# paste_injectorMM.net
KiCad netlist of a schematic drawn in EAGLE
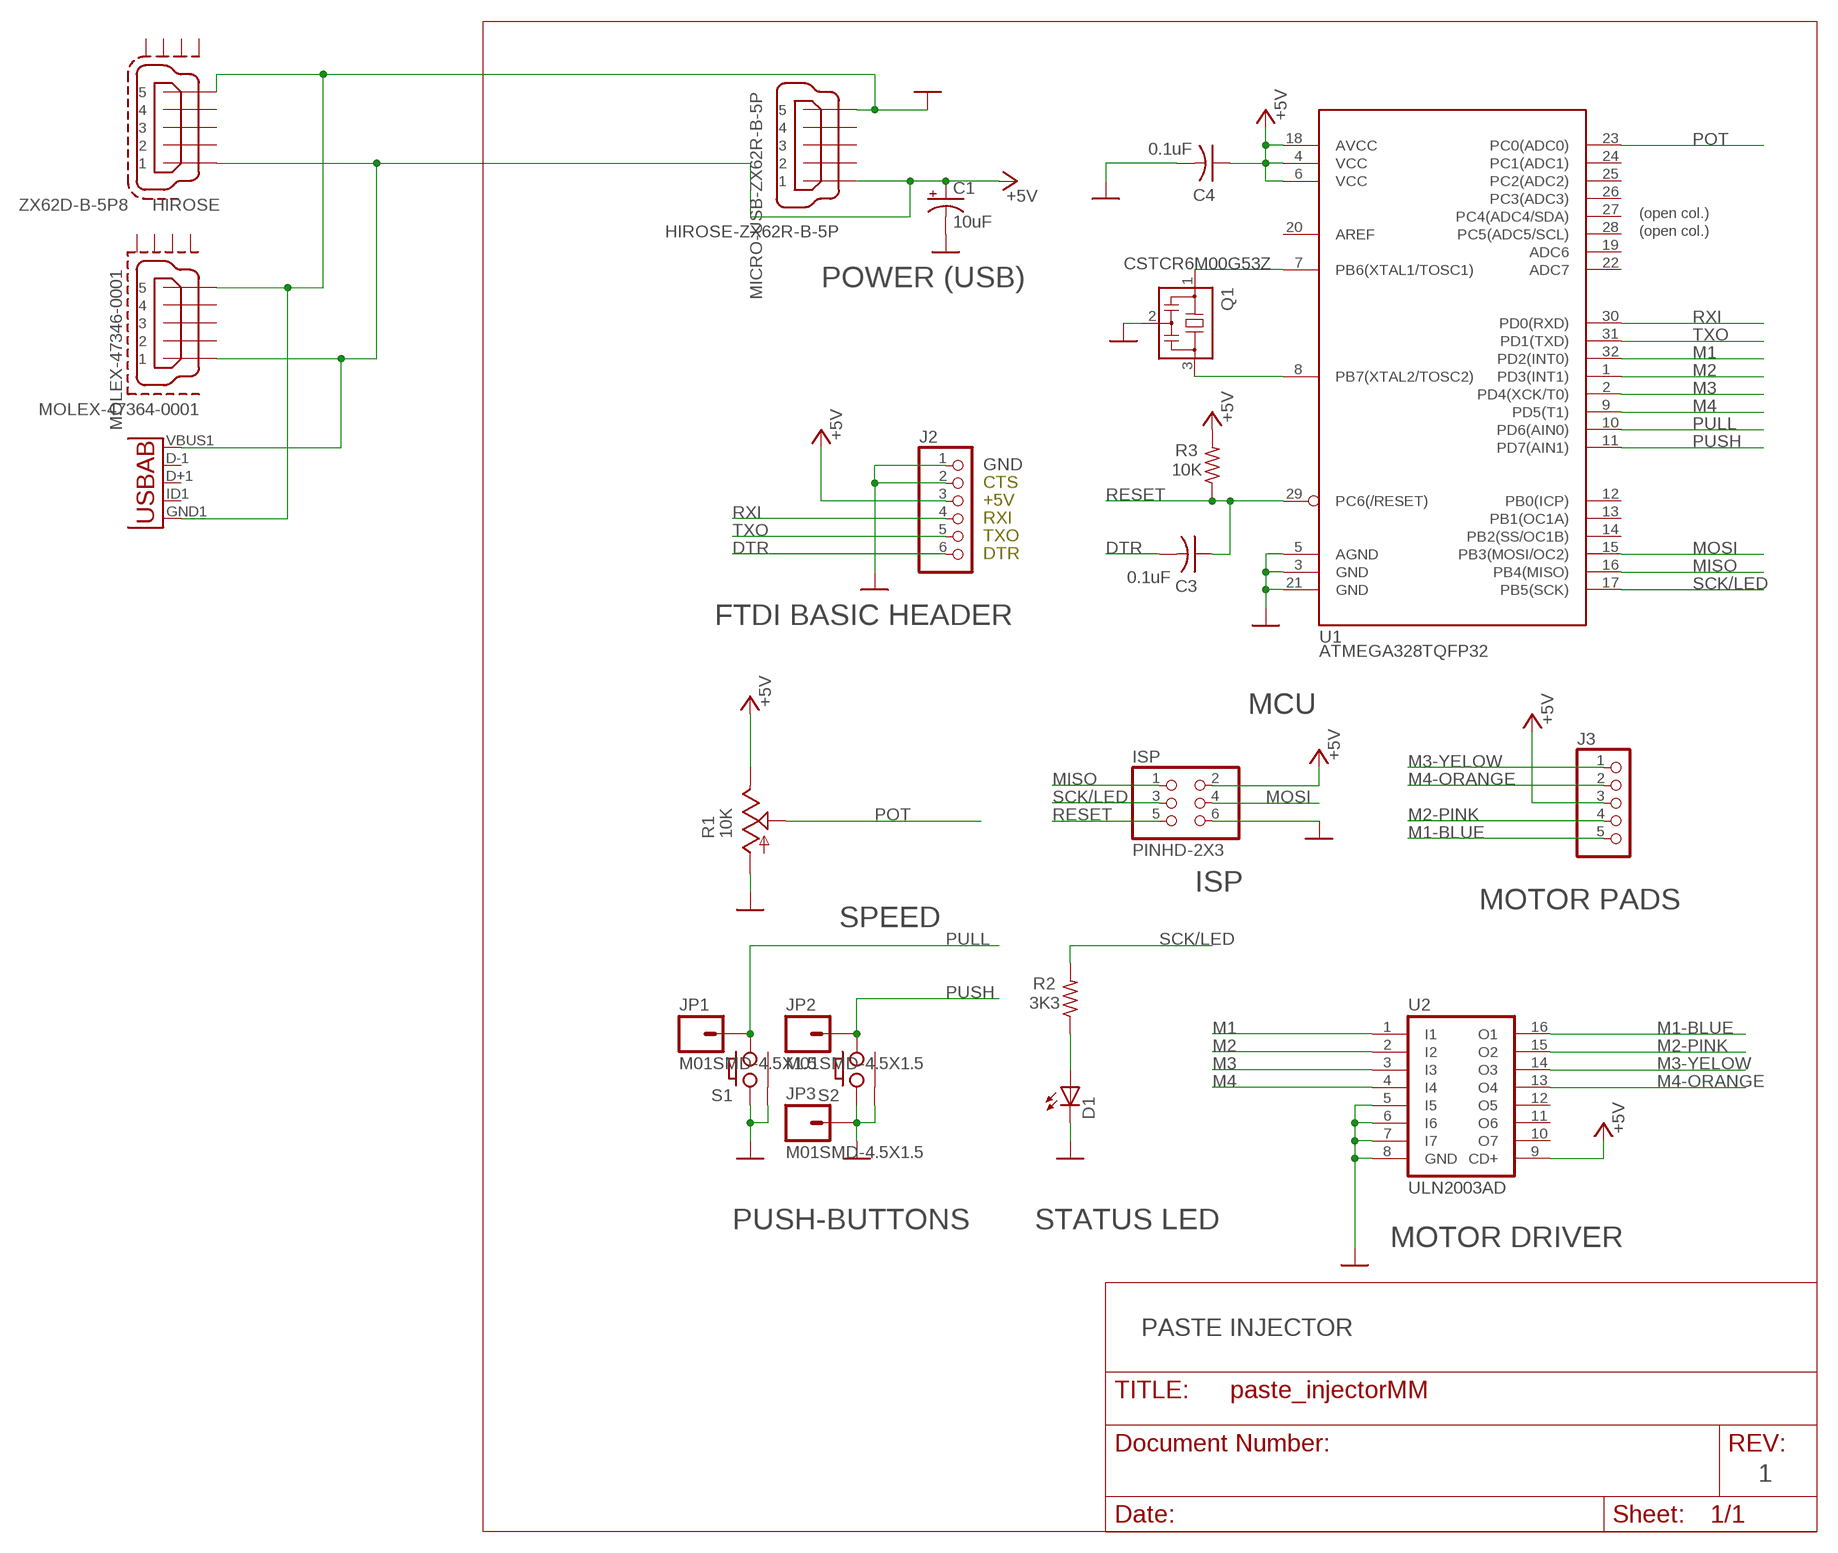
[diagram p0: schematic, sheet 1]

(export (version "E")
  (design (tool "Eeschema 10.0.6"))
  (components
    (comp (ref "C1")
      (value "10uF")
      (footprint "eagle-import:A_3216-18R")
      (libsource (lib "eagle-import") (part "CPOL-USA/3216-18R"))
    )
    (comp (ref "C3")
      (value "0.1uF")
      (footprint "eagle-import:C0603")
      (libsource (lib "eagle-import") (part "CAP-C0603"))
    )
    (comp (ref "C4")
      (value "0.1uF")
      (footprint "eagle-import:C0603")
      (libsource (lib "eagle-import") (part "CAP-C0603"))
    )
    (comp (ref "D1")
      (value "LED")
      (footprint "eagle-import:LED0603")
      (libsource (lib "eagle-import") (part "LED"))
    )
    (comp (ref "HIROSE")
      (value "ZX62D-B-5P8")
      (footprint "eagle-import:ZX62D-B-5P8")
      (libsource (lib "eagle-import") (part "ZX62D-B-5P8"))
    )
    (comp (ref "HIROSE-ZX62R-B-5P")
      (value "MICRO-USB-ZX62R-B-5P")
      (footprint "eagle-import:ZX62R-B-5P")
      (libsource (lib "eagle-import") (part "MICRO-USB-ZX62R-B-5P"))
    )
    (comp (ref "ISP")
      (value "PINHD-2X3")
      (footprint "eagle-import:2X03")
      (libsource (lib "eagle-import") (part "PINHD-2X3"))
    )
    (comp (ref "J2")
      (value "PINHD-1X6")
      (footprint "eagle-import:1X06")
      (libsource (lib "eagle-import") (part "PINHD-1X6"))
    )
    (comp (ref "J3")
      (value "PINHD-1X5")
      (footprint "eagle-import:1X05")
      (libsource (lib "eagle-import") (part "PINHD-1X5"))
    )
    (comp (ref "JP1")
      (value "M01SMD-4.5X1.5")
      (footprint "eagle-import:PAD-1.5X4.5")
      (libsource (lib "eagle-import") (part "M01SMD-4.5X1.5"))
    )
    (comp (ref "JP2")
      (value "M01SMD-4.5X1.5")
      (footprint "eagle-import:PAD-1.5X4.5")
      (libsource (lib "eagle-import") (part "M01SMD-4.5X1.5"))
    )
    (comp (ref "JP3")
      (value "M01SMD-4.5X1.5")
      (footprint "eagle-import:PAD-1.5X4.5")
      (libsource (lib "eagle-import") (part "M01SMD-4.5X1.5"))
    )
    (comp (ref "MOLEX-47364-0001")
      (value "MOLEX-47346-0001")
      (footprint "eagle-import:MOLEX-47364-0001")
      (libsource (lib "eagle-import") (part "MOLEX-47346-0001"))
    )
    (comp (ref "Q1")
      (value "CSTCR6M00G53Z")
      (footprint "eagle-import:CSTCR6M")
      (fields (field (name "MPN") "CSTCR6M00G53-R0"))
      (libsource (lib "eagle-import") (part "CSTCR6M00G53Z"))
    )
    (comp (ref "R1")
      (value "10K")
      (footprint "eagle-import:TRIMPOT")
      (libsource (lib "eagle-import") (part "TRIMPOTCA9V"))
    )
    (comp (ref "R2")
      (value "3K3")
      (footprint "eagle-import:R0603")
      (libsource (lib "eagle-import") (part "RES-R0603"))
    )
    (comp (ref "R3")
      (value "10K")
      (footprint "eagle-import:R0603")
      (libsource (lib "eagle-import") (part "RES-R0603"))
    )
    (comp (ref "S1")
      (value "PUSH_BUTTON")
      (footprint "eagle-import:PUSH_BUTTON")
      (libsource (lib "eagle-import") (part "PUSH_BUTTON"))
    )
    (comp (ref "S2")
      (value "PUSH_BUTTON")
      (footprint "eagle-import:PUSH_BUTTON")
      (libsource (lib "eagle-import") (part "PUSH_BUTTON"))
    )
    (comp (ref "U$7")
      (value "USB-AB\"\"")
      (footprint "eagle-import:USB-AB-MICRO-SMD_V02_BOSS")
      (libsource (lib "eagle-import") (part "USB-AB{dblquote}{dblquote}"))
    )
    (comp (ref "U1")
      (value "ATMEGA328TQFP32")
      (footprint "eagle-import:TQFP32-08")
      (libsource (lib "eagle-import") (part "ATMEGA328TQFP32"))
    )
    (comp (ref "U2")
      (value "ULN2003AD")
      (footprint "eagle-import:SO16")
      (libsource (lib "eagle-import") (part "ULN2003AD"))
    )
  )
  (nets
    (net (code "1") (name "+5V") (class "Default")
      (node (ref "C1") (pin "+") (pinfunction "+_+") (pintype "passive"))
      (node (ref "C4") (pin "1") (pinfunction "1_1") (pintype "passive"))
      (node (ref "HIROSE") (pin "P$1") (pinfunction "1_P$1") (pintype "passive"))
      (node (ref "HIROSE-ZX62R-B-5P") (pin "1") (pinfunction "1_1") (pintype "input"))
      (node (ref "ISP") (pin "2") (pinfunction "2_2") (pintype "passive"))
      (node (ref "J2") (pin "3") (pinfunction "3_3") (pintype "passive"))
      (node (ref "J3") (pin "3") (pinfunction "3_3") (pintype "passive"))
      (node (ref "MOLEX-47364-0001") (pin "1") (pinfunction "1_1") (pintype "input"))
      (node (ref "R1") (pin "CW") (pinfunction "CW_CW") (pintype "passive"))
      (node (ref "R3") (pin "2") (pinfunction "2_2") (pintype "passive"))
      (node (ref "U$7") (pin "VBUS1") (pinfunction "VBUS_VBUS1") (pintype "bidirectional"))
      (node (ref "U1") (pin "18") (pinfunction "AVCC_18") (pintype "power_in"))
      (node (ref "U1") (pin "4") (pinfunction "VCC_4") (pintype "power_in"))
      (node (ref "U1") (pin "6") (pinfunction "VCC_6") (pintype "power_in"))
      (node (ref "U2") (pin "9") (pinfunction "CD+_9") (pintype "passive"))
    )
    (net (code "2") (name "/AREF") (class "Default")
      (node (ref "U1") (pin "20") (pinfunction "AREF_20") (pintype "power_in"))
    )
    (net (code "3") (name "/DTR") (class "Default")
      (node (ref "C3") (pin "2") (pinfunction "2_2") (pintype "passive"))
      (node (ref "J2") (pin "6") (pinfunction "6_6") (pintype "passive"))
    )
    (net (code "4") (name "/M1") (class "Default")
      (node (ref "U1") (pin "32") (pinfunction "PD2(INT0)_32") (pintype "bidirectional"))
      (node (ref "U2") (pin "1") (pinfunction "I1_1") (pintype "input"))
    )
    (net (code "5") (name "/M1-BLUE") (class "Default")
      (node (ref "J3") (pin "5") (pinfunction "5_5") (pintype "passive"))
      (node (ref "U2") (pin "16") (pinfunction "O1_16") (pintype "open_collector"))
    )
    (net (code "6") (name "/M2") (class "Default")
      (node (ref "U1") (pin "1") (pinfunction "PD3(INT1)_1") (pintype "bidirectional"))
      (node (ref "U2") (pin "2") (pinfunction "I2_2") (pintype "input"))
    )
    (net (code "7") (name "/M2-PINK") (class "Default")
      (node (ref "J3") (pin "4") (pinfunction "4_4") (pintype "passive"))
      (node (ref "U2") (pin "15") (pinfunction "O2_15") (pintype "open_collector"))
    )
    (net (code "8") (name "/M3") (class "Default")
      (node (ref "U1") (pin "2") (pinfunction "PD4(XCK/T0)_2") (pintype "bidirectional"))
      (node (ref "U2") (pin "3") (pinfunction "I3_3") (pintype "input"))
    )
    (net (code "9") (name "/M3-YELOW") (class "Default")
      (node (ref "J3") (pin "1") (pinfunction "1_1") (pintype "passive"))
      (node (ref "U2") (pin "14") (pinfunction "O3_14") (pintype "open_collector"))
    )
    (net (code "10") (name "/M4") (class "Default")
      (node (ref "U1") (pin "9") (pinfunction "PD5(T1)_9") (pintype "bidirectional"))
      (node (ref "U2") (pin "4") (pinfunction "I4_4") (pintype "input"))
    )
    (net (code "11") (name "/M4-ORANGE") (class "Default")
      (node (ref "J3") (pin "2") (pinfunction "2_2") (pintype "passive"))
      (node (ref "U2") (pin "13") (pinfunction "O4_13") (pintype "open_collector"))
    )
    (net (code "12") (name "/MISO") (class "Default")
      (node (ref "ISP") (pin "1") (pinfunction "1_1") (pintype "passive"))
      (node (ref "U1") (pin "16") (pinfunction "PB4(MISO)_16") (pintype "bidirectional"))
    )
    (net (code "13") (name "/MOSI") (class "Default")
      (node (ref "ISP") (pin "4") (pinfunction "4_4") (pintype "passive"))
      (node (ref "U1") (pin "15") (pinfunction "PB3(MOSI/OC2)_15") (pintype "bidirectional"))
    )
    (net (code "14") (name "/POT") (class "Default")
      (node (ref "R1") (pin "C") (pinfunction "C_C") (pintype "passive"))
      (node (ref "U1") (pin "23") (pinfunction "PC0(ADC0)_23") (pintype "bidirectional"))
    )
    (net (code "15") (name "/PULL") (class "Default")
      (node (ref "JP1") (pin "P$1") (pinfunction "1_P$1") (pintype "passive"))
      (node (ref "S1") (pin "B1") (pinfunction "2_B1") (pintype "passive"))
      (node (ref "U1") (pin "10") (pinfunction "PD6(AIN0)_10") (pintype "bidirectional"))
    )
    (net (code "16") (name "/PUSH") (class "Default")
      (node (ref "JP2") (pin "P$1") (pinfunction "1_P$1") (pintype "passive"))
      (node (ref "S2") (pin "B1") (pinfunction "2_B1") (pintype "passive"))
      (node (ref "U1") (pin "11") (pinfunction "PD7(AIN1)_11") (pintype "bidirectional"))
    )
    (net (code "17") (name "/RESET") (class "Default")
      (node (ref "C3") (pin "1") (pinfunction "1_1") (pintype "passive"))
      (node (ref "ISP") (pin "5") (pinfunction "5_5") (pintype "passive"))
      (node (ref "R3") (pin "1") (pinfunction "1_1") (pintype "passive"))
      (node (ref "U1") (pin "29") (pinfunction "PC6(/RESET)_29") (pintype "bidirectional"))
    )
    (net (code "18") (name "/RXI") (class "Default")
      (node (ref "J2") (pin "4") (pinfunction "4_4") (pintype "passive"))
      (node (ref "U1") (pin "30") (pinfunction "PD0(RXD)_30") (pintype "bidirectional"))
    )
    (net (code "19") (name "/SCK{slash}LED") (class "Default")
      (node (ref "ISP") (pin "3") (pinfunction "3_3") (pintype "passive"))
      (node (ref "R2") (pin "2") (pinfunction "2_2") (pintype "passive"))
      (node (ref "U1") (pin "17") (pinfunction "PB5(SCK)_17") (pintype "bidirectional"))
    )
    (net (code "20") (name "/TXO") (class "Default")
      (node (ref "J2") (pin "5") (pinfunction "5_5") (pintype "passive"))
      (node (ref "U1") (pin "31") (pinfunction "PD1(TXD)_31") (pintype "bidirectional"))
    )
    (net (code "21") (name "GND") (class "Default")
      (node (ref "C1") (pin "-") (pinfunction "-_-") (pintype "passive"))
      (node (ref "C4") (pin "2") (pinfunction "2_2") (pintype "passive"))
      (node (ref "D1") (pin "C") (pinfunction "C_C") (pintype "passive"))
      (node (ref "HIROSE") (pin "P$5") (pinfunction "5_P$5") (pintype "passive"))
      (node (ref "HIROSE-ZX62R-B-5P") (pin "5") (pinfunction "5_5") (pintype "input"))
      (node (ref "ISP") (pin "6") (pinfunction "6_6") (pintype "passive"))
      (node (ref "J2") (pin "1") (pinfunction "1_1") (pintype "passive"))
      (node (ref "J2") (pin "2") (pinfunction "2_2") (pintype "passive"))
      (node (ref "JP3") (pin "P$1") (pinfunction "1_P$1") (pintype "passive"))
      (node (ref "MOLEX-47364-0001") (pin "5") (pinfunction "5_5") (pintype "input"))
      (node (ref "Q1") (pin "2") (pinfunction "2_2") (pintype "passive"))
      (node (ref "R1") (pin "CCW") (pinfunction "CCW_CCW") (pintype "passive"))
      (node (ref "S1") (pin "A1") (pinfunction "1_A1") (pintype "passive"))
      (node (ref "S1") (pin "GND") (pinfunction "GND_GND") (pintype "power_in"))
      (node (ref "S2") (pin "A1") (pinfunction "1_A1") (pintype "passive"))
      (node (ref "S2") (pin "GND") (pinfunction "GND_GND") (pintype "power_in"))
      (node (ref "U$7") (pin "GND1") (pinfunction "GND_GND1") (pintype "bidirectional"))
      (node (ref "U1") (pin "21") (pinfunction "GND_21") (pintype "power_in"))
      (node (ref "U1") (pin "3") (pinfunction "GND_3") (pintype "power_in"))
      (node (ref "U1") (pin "5") (pinfunction "AGND_5") (pintype "power_in"))
      (node (ref "U2") (pin "5") (pinfunction "I5_5") (pintype "input"))
      (node (ref "U2") (pin "6") (pinfunction "I6_6") (pintype "input"))
      (node (ref "U2") (pin "7") (pinfunction "I7_7") (pintype "input"))
      (node (ref "U2") (pin "8") (pinfunction "GND_8") (pintype "power_in"))
    )
    (net (code "22") (name "Net-(D1-PadA)") (class "Default")
      (node (ref "D1") (pin "A") (pinfunction "A_A") (pintype "passive"))
      (node (ref "R2") (pin "1") (pinfunction "1_1") (pintype "passive"))
    )
    (net (code "23") (name "Net-(U1-PB6(XTAL1{slash}TOSC1))") (class "Default")
      (node (ref "Q1") (pin "1") (pinfunction "1_1") (pintype "passive"))
      (node (ref "U1") (pin "7") (pinfunction "PB6(XTAL1/TOSC1)_7") (pintype "bidirectional"))
    )
    (net (code "24") (name "Net-(U1-PB7(XTAL2{slash}TOSC2))") (class "Default")
      (node (ref "Q1") (pin "3") (pinfunction "3_3") (pintype "passive"))
      (node (ref "U1") (pin "8") (pinfunction "PB7(XTAL2/TOSC2)_8") (pintype "bidirectional"))
    )
    (net (code "25") (name "unconnected-(HIROSE-2-PadP$2)") (class "Default")
      (node (ref "HIROSE") (pin "P$2") (pinfunction "2_P$2") (pintype "passive"))
    )
    (net (code "26") (name "unconnected-(HIROSE-3-PadP$3)") (class "Default")
      (node (ref "HIROSE") (pin "P$3") (pinfunction "3_P$3") (pintype "passive"))
    )
    (net (code "27") (name "unconnected-(HIROSE-4-PadP$4)") (class "Default")
      (node (ref "HIROSE") (pin "P$4") (pinfunction "4_P$4") (pintype "passive"))
    )
    (net (code "28") (name "unconnected-(HIROSE-PadSH1)") (class "Default")
      (node (ref "HIROSE") (pin "SH1") (pinfunction "SH1_SH1") (pintype "passive"))
    )
    (net (code "29") (name "unconnected-(HIROSE-PadSH2)") (class "Default")
      (node (ref "HIROSE") (pin "SH2") (pinfunction "SH2_SH2") (pintype "passive"))
    )
    (net (code "30") (name "unconnected-(HIROSE-PadSH3)") (class "Default")
      (node (ref "HIROSE") (pin "SH3") (pinfunction "SH3_SH3") (pintype "passive"))
    )
    (net (code "31") (name "unconnected-(HIROSE-PadSH4)") (class "Default")
      (node (ref "HIROSE") (pin "SH4") (pinfunction "SH4_SH4") (pintype "passive"))
    )
    (net (code "32") (name "unconnected-(HIROSE-ZX62R-B-5P-Pad2)") (class "Default")
      (node (ref "HIROSE-ZX62R-B-5P") (pin "2") (pinfunction "2_2") (pintype "input"))
    )
    (net (code "33") (name "unconnected-(HIROSE-ZX62R-B-5P-Pad3)") (class "Default")
      (node (ref "HIROSE-ZX62R-B-5P") (pin "3") (pinfunction "3_3") (pintype "input"))
    )
    (net (code "34") (name "unconnected-(HIROSE-ZX62R-B-5P-Pad4)") (class "Default")
      (node (ref "HIROSE-ZX62R-B-5P") (pin "4") (pinfunction "4_4") (pintype "input"))
    )
    (net (code "35") (name "unconnected-(MOLEX-47364-0001-Pad2)") (class "Default")
      (node (ref "MOLEX-47364-0001") (pin "2") (pinfunction "2_2") (pintype "input"))
    )
    (net (code "36") (name "unconnected-(MOLEX-47364-0001-Pad3)") (class "Default")
      (node (ref "MOLEX-47364-0001") (pin "3") (pinfunction "3_3") (pintype "input"))
    )
    (net (code "37") (name "unconnected-(MOLEX-47364-0001-Pad4)") (class "Default")
      (node (ref "MOLEX-47364-0001") (pin "4") (pinfunction "4_4") (pintype "input"))
    )
    (net (code "38") (name "unconnected-(MOLEX-47364-0001-PadGND1)") (class "Default")
      (node (ref "MOLEX-47364-0001") (pin "GND1") (pinfunction "GND1_GND1") (pintype "bidirectional"))
    )
    (net (code "39") (name "unconnected-(MOLEX-47364-0001-PadGND2)") (class "Default")
      (node (ref "MOLEX-47364-0001") (pin "GND2") (pinfunction "GND2_GND2") (pintype "bidirectional"))
    )
    (net (code "40") (name "unconnected-(MOLEX-47364-0001-PadGND3)") (class "Default")
      (node (ref "MOLEX-47364-0001") (pin "GND3") (pinfunction "GND3_GND3") (pintype "bidirectional"))
    )
    (net (code "41") (name "unconnected-(MOLEX-47364-0001-PadGND4)") (class "Default")
      (node (ref "MOLEX-47364-0001") (pin "GND4") (pinfunction "GND4_GND4") (pintype "bidirectional"))
    )
    (net (code "42") (name "unconnected-(U$7-D+-PadD+1)") (class "Default")
      (node (ref "U$7") (pin "D+1") (pinfunction "D+_D+1") (pintype "bidirectional"))
    )
    (net (code "43") (name "unconnected-(U$7-D--PadD-1)") (class "Default")
      (node (ref "U$7") (pin "D-1") (pinfunction "D-_D-1") (pintype "bidirectional"))
    )
    (net (code "44") (name "unconnected-(U$7-USBID-PadID1)") (class "Default")
      (node (ref "U$7") (pin "ID1") (pinfunction "USBID_ID1") (pintype "bidirectional"))
    )
    (net (code "45") (name "unconnected-(U1-ADC6-Pad19)") (class "Default")
      (node (ref "U1") (pin "19") (pinfunction "ADC6_19") (pintype "bidirectional"))
    )
    (net (code "46") (name "unconnected-(U1-ADC7-Pad22)") (class "Default")
      (node (ref "U1") (pin "22") (pinfunction "ADC7_22") (pintype "bidirectional"))
    )
    (net (code "47") (name "unconnected-(U1-PB0(ICP)-Pad12)") (class "Default")
      (node (ref "U1") (pin "12") (pinfunction "PB0(ICP)_12") (pintype "bidirectional"))
    )
    (net (code "48") (name "unconnected-(U1-PB1(OC1A)-Pad13)") (class "Default")
      (node (ref "U1") (pin "13") (pinfunction "PB1(OC1A)_13") (pintype "bidirectional"))
    )
    (net (code "49") (name "unconnected-(U1-PB2(SS{slash}OC1B)-Pad14)") (class "Default")
      (node (ref "U1") (pin "14") (pinfunction "PB2(SS/OC1B)_14") (pintype "bidirectional"))
    )
    (net (code "50") (name "unconnected-(U1-PC1(ADC1)-Pad24)") (class "Default")
      (node (ref "U1") (pin "24") (pinfunction "PC1(ADC1)_24") (pintype "bidirectional"))
    )
    (net (code "51") (name "unconnected-(U1-PC2(ADC2)-Pad25)") (class "Default")
      (node (ref "U1") (pin "25") (pinfunction "PC2(ADC2)_25") (pintype "bidirectional"))
    )
    (net (code "52") (name "unconnected-(U1-PC3(ADC3)-Pad26)") (class "Default")
      (node (ref "U1") (pin "26") (pinfunction "PC3(ADC3)_26") (pintype "bidirectional"))
    )
    (net (code "53") (name "unconnected-(U1-PC4(ADC4{slash}SDA)-Pad27)") (class "Default")
      (node (ref "U1") (pin "27") (pinfunction "PC4(ADC4/SDA)_27") (pintype "bidirectional"))
    )
    (net (code "54") (name "unconnected-(U1-PC5(ADC5{slash}SCL)-Pad28)") (class "Default")
      (node (ref "U1") (pin "28") (pinfunction "PC5(ADC5/SCL)_28") (pintype "bidirectional"))
    )
    (net (code "55") (name "unconnected-(U2-O5-Pad12)") (class "Default")
      (node (ref "U2") (pin "12") (pinfunction "O5_12") (pintype "open_collector"))
    )
    (net (code "56") (name "unconnected-(U2-O6-Pad11)") (class "Default")
      (node (ref "U2") (pin "11") (pinfunction "O6_11") (pintype "open_collector"))
    )
    (net (code "57") (name "unconnected-(U2-O7-Pad10)") (class "Default")
      (node (ref "U2") (pin "10") (pinfunction "O7_10") (pintype "open_collector"))
    )
  )
)
